# arduino-pro-mini_2-way-switches_v0_2_2.net
KiCad netlist of a schematic drawn in EAGLE
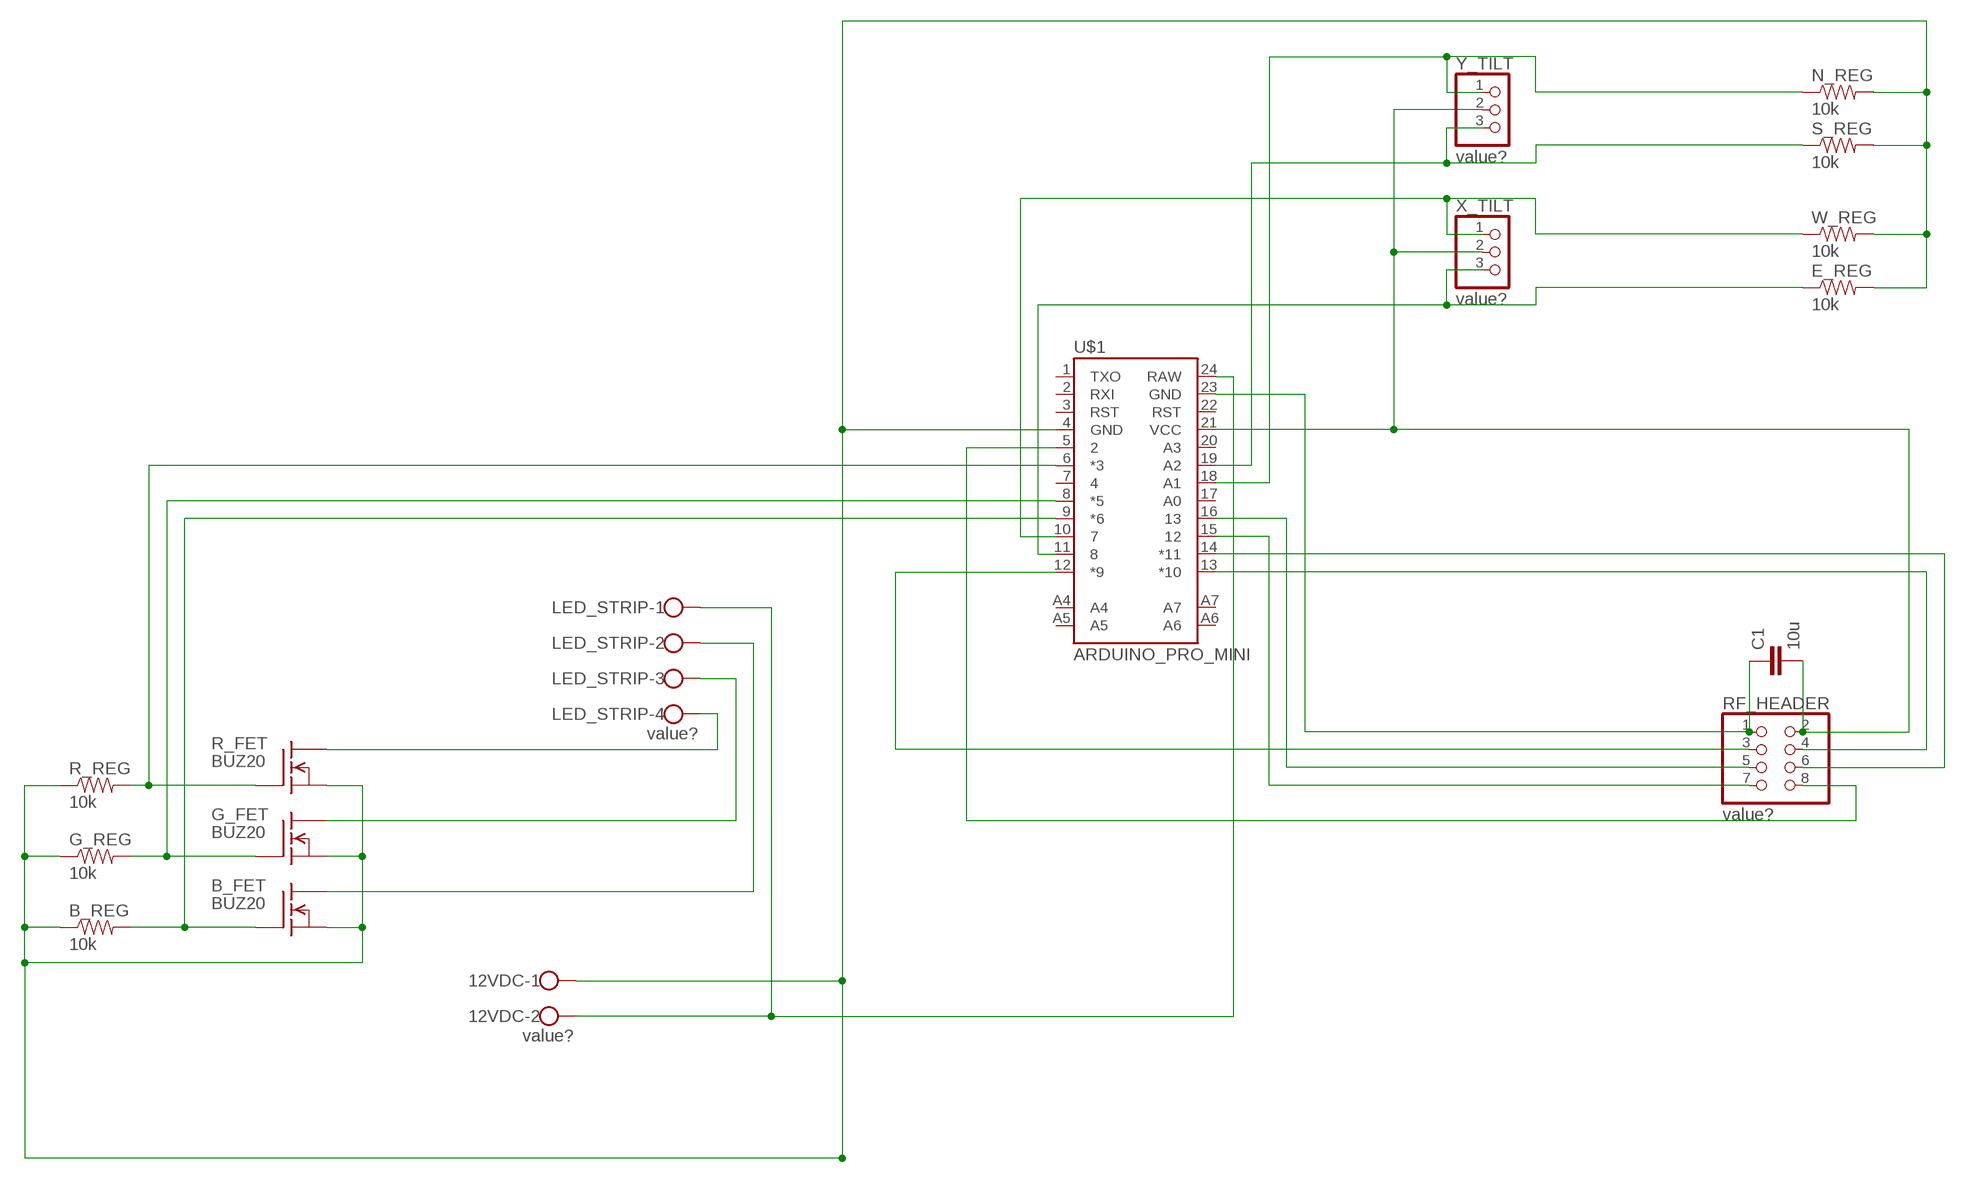
[diagram p0: schematic, sheet 1]

(export (version "E")
  (design (tool "Eeschema 10.0.6"))
  (components
    (comp (ref "12VDC")
      (value "value?")
      (footprint "eagle-import:W237-102")
      (fields (field (name "MPN") "237-102"))
      (libsource (lib "eagle-import") (part "W237-102"))
    )
    (comp (ref "B_FET")
      (value "BUZ20")
      (footprint "eagle-import:TO220")
      (libsource (lib "eagle-import") (part "BUZ20"))
    )
    (comp (ref "B_REG")
      (value "10k")
      (footprint "eagle-import:AXIAL-0.4")
      (libsource (lib "eagle-import") (part "RESISTORPTH-1/4W"))
    )
    (comp (ref "C1")
      (value "10u")
      (footprint "eagle-import:CAP-PTH-SMALL")
      (libsource (lib "eagle-import") (part "CAPPTH"))
    )
    (comp (ref "E_REG")
      (value "10k")
      (footprint "eagle-import:AXIAL-0.4")
      (libsource (lib "eagle-import") (part "RESISTORPTH-1/4W"))
    )
    (comp (ref "G_FET")
      (value "BUZ20")
      (footprint "eagle-import:TO220")
      (libsource (lib "eagle-import") (part "BUZ20"))
    )
    (comp (ref "G_REG")
      (value "10k")
      (footprint "eagle-import:AXIAL-0.4")
      (libsource (lib "eagle-import") (part "RESISTORPTH-1/4W"))
    )
    (comp (ref "LED_STRIP")
      (value "value?")
      (footprint "eagle-import:W237-4")
      (libsource (lib "eagle-import") (part "W237-4"))
    )
    (comp (ref "N_REG")
      (value "10k")
      (footprint "eagle-import:AXIAL-0.4")
      (libsource (lib "eagle-import") (part "RESISTORPTH-1/4W"))
    )
    (comp (ref "RF_HEADER")
      (value "value?")
      (footprint "eagle-import:2X04")
      (libsource (lib "eagle-import") (part "PINHD-2X4"))
    )
    (comp (ref "R_FET")
      (value "BUZ20")
      (footprint "eagle-import:TO220")
      (libsource (lib "eagle-import") (part "BUZ20"))
    )
    (comp (ref "R_REG")
      (value "10k")
      (footprint "eagle-import:AXIAL-0.4")
      (libsource (lib "eagle-import") (part "RESISTORPTH-1/4W"))
    )
    (comp (ref "S_REG")
      (value "10k")
      (footprint "eagle-import:AXIAL-0.4")
      (libsource (lib "eagle-import") (part "RESISTORPTH-1/4W"))
    )
    (comp (ref "U$1")
      (value "ARDUINO_PRO_MINI")
      (footprint "eagle-import:ARDUINO_PRO_MINI")
      (libsource (lib "eagle-import") (part "ARDUINO_PRO_MINI"))
    )
    (comp (ref "W_REG")
      (value "10k")
      (footprint "eagle-import:AXIAL-0.4")
      (libsource (lib "eagle-import") (part "RESISTORPTH-1/4W"))
    )
    (comp (ref "X_TILT")
      (value "value?")
      (footprint "eagle-import:1X03")
      (libsource (lib "eagle-import") (part "PINHD-1X3"))
    )
    (comp (ref "Y_TILT")
      (value "value?")
      (footprint "eagle-import:1X03")
      (libsource (lib "eagle-import") (part "PINHD-1X3"))
    )
  )
  (nets
    (net (code "1") (name "Net-(12VDCA-KL)") (class "Default")
      (node (ref "12VDC") (pin "1") (pinfunction "KL_1") (pintype "passive"))
      (node (ref "B_FET") (pin "3") (pinfunction "S_3") (pintype "passive"))
      (node (ref "B_REG") (pin "P$1") (pinfunction "1_P$1") (pintype "passive"))
      (node (ref "E_REG") (pin "P$2") (pinfunction "2_P$2") (pintype "passive"))
      (node (ref "G_FET") (pin "3") (pinfunction "S_3") (pintype "passive"))
      (node (ref "G_REG") (pin "P$1") (pinfunction "1_P$1") (pintype "passive"))
      (node (ref "N_REG") (pin "P$2") (pinfunction "2_P$2") (pintype "passive"))
      (node (ref "R_FET") (pin "3") (pinfunction "S_3") (pintype "passive"))
      (node (ref "R_REG") (pin "P$1") (pinfunction "1_P$1") (pintype "passive"))
      (node (ref "S_REG") (pin "P$2") (pinfunction "2_P$2") (pintype "passive"))
      (node (ref "U$1") (pin "4") (pinfunction "GND_4") (pintype "bidirectional"))
      (node (ref "W_REG") (pin "P$2") (pinfunction "2_P$2") (pintype "passive"))
    )
    (net (code "2") (name "Net-(12VDCB-KL)") (class "Default")
      (node (ref "12VDC") (pin "2") (pinfunction "KL_2") (pintype "passive"))
      (node (ref "LED_STRIP") (pin "1") (pinfunction "KL_1") (pintype "passive"))
      (node (ref "U$1") (pin "24") (pinfunction "RAW_24") (pintype "bidirectional"))
    )
    (net (code "3") (name "Net-(B_FET-D)") (class "Default")
      (node (ref "B_FET") (pin "2") (pinfunction "D_2") (pintype "passive"))
      (node (ref "LED_STRIP") (pin "2") (pinfunction "KL_2") (pintype "passive"))
    )
    (net (code "4") (name "Net-(B_FET-G)") (class "Default")
      (node (ref "B_FET") (pin "1") (pinfunction "G_1") (pintype "passive"))
      (node (ref "B_REG") (pin "P$2") (pinfunction "2_P$2") (pintype "passive"))
      (node (ref "U$1") (pin "9") (pinfunction "*6_9") (pintype "bidirectional"))
    )
    (net (code "5") (name "Net-(C1-Pad1)") (class "Default")
      (node (ref "C1") (pin "1") (pinfunction "1_1") (pintype "passive"))
      (node (ref "RF_HEADER") (pin "1") (pinfunction "1_1") (pintype "passive"))
      (node (ref "U$1") (pin "23") (pinfunction "GND_23") (pintype "bidirectional"))
    )
    (net (code "6") (name "Net-(E_REG-1)") (class "Default")
      (node (ref "E_REG") (pin "P$1") (pinfunction "1_P$1") (pintype "passive"))
      (node (ref "U$1") (pin "11") (pinfunction "8_11") (pintype "bidirectional"))
      (node (ref "X_TILT") (pin "3") (pinfunction "3_3") (pintype "passive"))
    )
    (net (code "7") (name "Net-(G_FET-D)") (class "Default")
      (node (ref "G_FET") (pin "2") (pinfunction "D_2") (pintype "passive"))
      (node (ref "LED_STRIP") (pin "3") (pinfunction "KL_3") (pintype "passive"))
    )
    (net (code "8") (name "Net-(G_FET-G)") (class "Default")
      (node (ref "G_FET") (pin "1") (pinfunction "G_1") (pintype "passive"))
      (node (ref "G_REG") (pin "P$2") (pinfunction "2_P$2") (pintype "passive"))
      (node (ref "U$1") (pin "8") (pinfunction "*5_8") (pintype "bidirectional"))
    )
    (net (code "9") (name "Net-(LED_STRIPD-KL)") (class "Default")
      (node (ref "LED_STRIP") (pin "4") (pinfunction "KL_4") (pintype "passive"))
      (node (ref "R_FET") (pin "2") (pinfunction "D_2") (pintype "passive"))
    )
    (net (code "10") (name "Net-(N_REG-1)") (class "Default")
      (node (ref "N_REG") (pin "P$1") (pinfunction "1_P$1") (pintype "passive"))
      (node (ref "U$1") (pin "18") (pinfunction "A1_18") (pintype "bidirectional"))
      (node (ref "Y_TILT") (pin "1") (pinfunction "1_1") (pintype "passive"))
    )
    (net (code "11") (name "Net-(R_FET-G)") (class "Default")
      (node (ref "R_FET") (pin "1") (pinfunction "G_1") (pintype "passive"))
      (node (ref "R_REG") (pin "P$2") (pinfunction "2_P$2") (pintype "passive"))
      (node (ref "U$1") (pin "6") (pinfunction "*3_6") (pintype "bidirectional"))
    )
    (net (code "12") (name "Net-(S_REG-1)") (class "Default")
      (node (ref "S_REG") (pin "P$1") (pinfunction "1_P$1") (pintype "passive"))
      (node (ref "U$1") (pin "19") (pinfunction "A2_19") (pintype "bidirectional"))
      (node (ref "Y_TILT") (pin "3") (pinfunction "3_3") (pintype "passive"))
    )
    (net (code "13") (name "Net-(U$1-*9)") (class "Default")
      (node (ref "RF_HEADER") (pin "3") (pinfunction "3_3") (pintype "passive"))
      (node (ref "U$1") (pin "12") (pinfunction "*9_12") (pintype "bidirectional"))
    )
    (net (code "14") (name "Net-(U$1-*10)") (class "Default")
      (node (ref "RF_HEADER") (pin "4") (pinfunction "4_4") (pintype "passive"))
      (node (ref "U$1") (pin "13") (pinfunction "*10_13") (pintype "bidirectional"))
    )
    (net (code "15") (name "Net-(U$1-*11)") (class "Default")
      (node (ref "RF_HEADER") (pin "6") (pinfunction "6_6") (pintype "passive"))
      (node (ref "U$1") (pin "14") (pinfunction "*11_14") (pintype "bidirectional"))
    )
    (net (code "16") (name "Net-(U$1-2)") (class "Default")
      (node (ref "RF_HEADER") (pin "8") (pinfunction "8_8") (pintype "passive"))
      (node (ref "U$1") (pin "5") (pinfunction "2_5") (pintype "bidirectional"))
    )
    (net (code "17") (name "Net-(U$1-7)") (class "Default")
      (node (ref "U$1") (pin "10") (pinfunction "7_10") (pintype "bidirectional"))
      (node (ref "W_REG") (pin "P$1") (pinfunction "1_P$1") (pintype "passive"))
      (node (ref "X_TILT") (pin "1") (pinfunction "1_1") (pintype "passive"))
    )
    (net (code "18") (name "Net-(U$1-12)") (class "Default")
      (node (ref "RF_HEADER") (pin "7") (pinfunction "7_7") (pintype "passive"))
      (node (ref "U$1") (pin "15") (pinfunction "12_15") (pintype "bidirectional"))
    )
    (net (code "19") (name "Net-(U$1-13)") (class "Default")
      (node (ref "RF_HEADER") (pin "5") (pinfunction "5_5") (pintype "passive"))
      (node (ref "U$1") (pin "16") (pinfunction "13_16") (pintype "bidirectional"))
    )
    (net (code "20") (name "Net-(U$1-VCC)") (class "Default")
      (node (ref "C1") (pin "2") (pinfunction "2_2") (pintype "passive"))
      (node (ref "RF_HEADER") (pin "2") (pinfunction "2_2") (pintype "passive"))
      (node (ref "U$1") (pin "21") (pinfunction "VCC_21") (pintype "bidirectional"))
      (node (ref "X_TILT") (pin "2") (pinfunction "2_2") (pintype "passive"))
      (node (ref "Y_TILT") (pin "2") (pinfunction "2_2") (pintype "passive"))
    )
    (net (code "21") (name "unconnected-(U$1-4-Pad7)") (class "Default")
      (node (ref "U$1") (pin "7") (pinfunction "4_7") (pintype "bidirectional"))
    )
    (net (code "22") (name "unconnected-(U$1-A0-Pad17)") (class "Default")
      (node (ref "U$1") (pin "17") (pinfunction "A0_17") (pintype "bidirectional"))
    )
    (net (code "23") (name "unconnected-(U$1-A3-Pad20)") (class "Default")
      (node (ref "U$1") (pin "20") (pinfunction "A3_20") (pintype "bidirectional"))
    )
    (net (code "24") (name "unconnected-(U$1-PadA4)") (class "Default")
      (node (ref "U$1") (pin "A4") (pinfunction "A4_A4") (pintype "bidirectional"))
    )
    (net (code "25") (name "unconnected-(U$1-PadA5)") (class "Default")
      (node (ref "U$1") (pin "A5") (pinfunction "A5_A5") (pintype "bidirectional"))
    )
    (net (code "26") (name "unconnected-(U$1-PadA6)") (class "Default")
      (node (ref "U$1") (pin "A6") (pinfunction "A6_A6") (pintype "bidirectional"))
    )
    (net (code "27") (name "unconnected-(U$1-PadA7)") (class "Default")
      (node (ref "U$1") (pin "A7") (pinfunction "A7_A7") (pintype "bidirectional"))
    )
    (net (code "28") (name "unconnected-(U$1-RST-Pad3)") (class "Default")
      (node (ref "U$1") (pin "3") (pinfunction "RST_3") (pintype "bidirectional"))
    )
    (net (code "29") (name "unconnected-(U$1-RST-Pad22)") (class "Default")
      (node (ref "U$1") (pin "22") (pinfunction "RST_22") (pintype "bidirectional"))
    )
    (net (code "30") (name "unconnected-(U$1-RXI-Pad2)") (class "Default")
      (node (ref "U$1") (pin "2") (pinfunction "RXI_2") (pintype "bidirectional"))
    )
    (net (code "31") (name "unconnected-(U$1-TXO-Pad1)") (class "Default")
      (node (ref "U$1") (pin "1") (pinfunction "TXO_1") (pintype "bidirectional"))
    )
  )
)
